# design.net
KiCad netlist of a schematic drawn in EasyEDA Pro
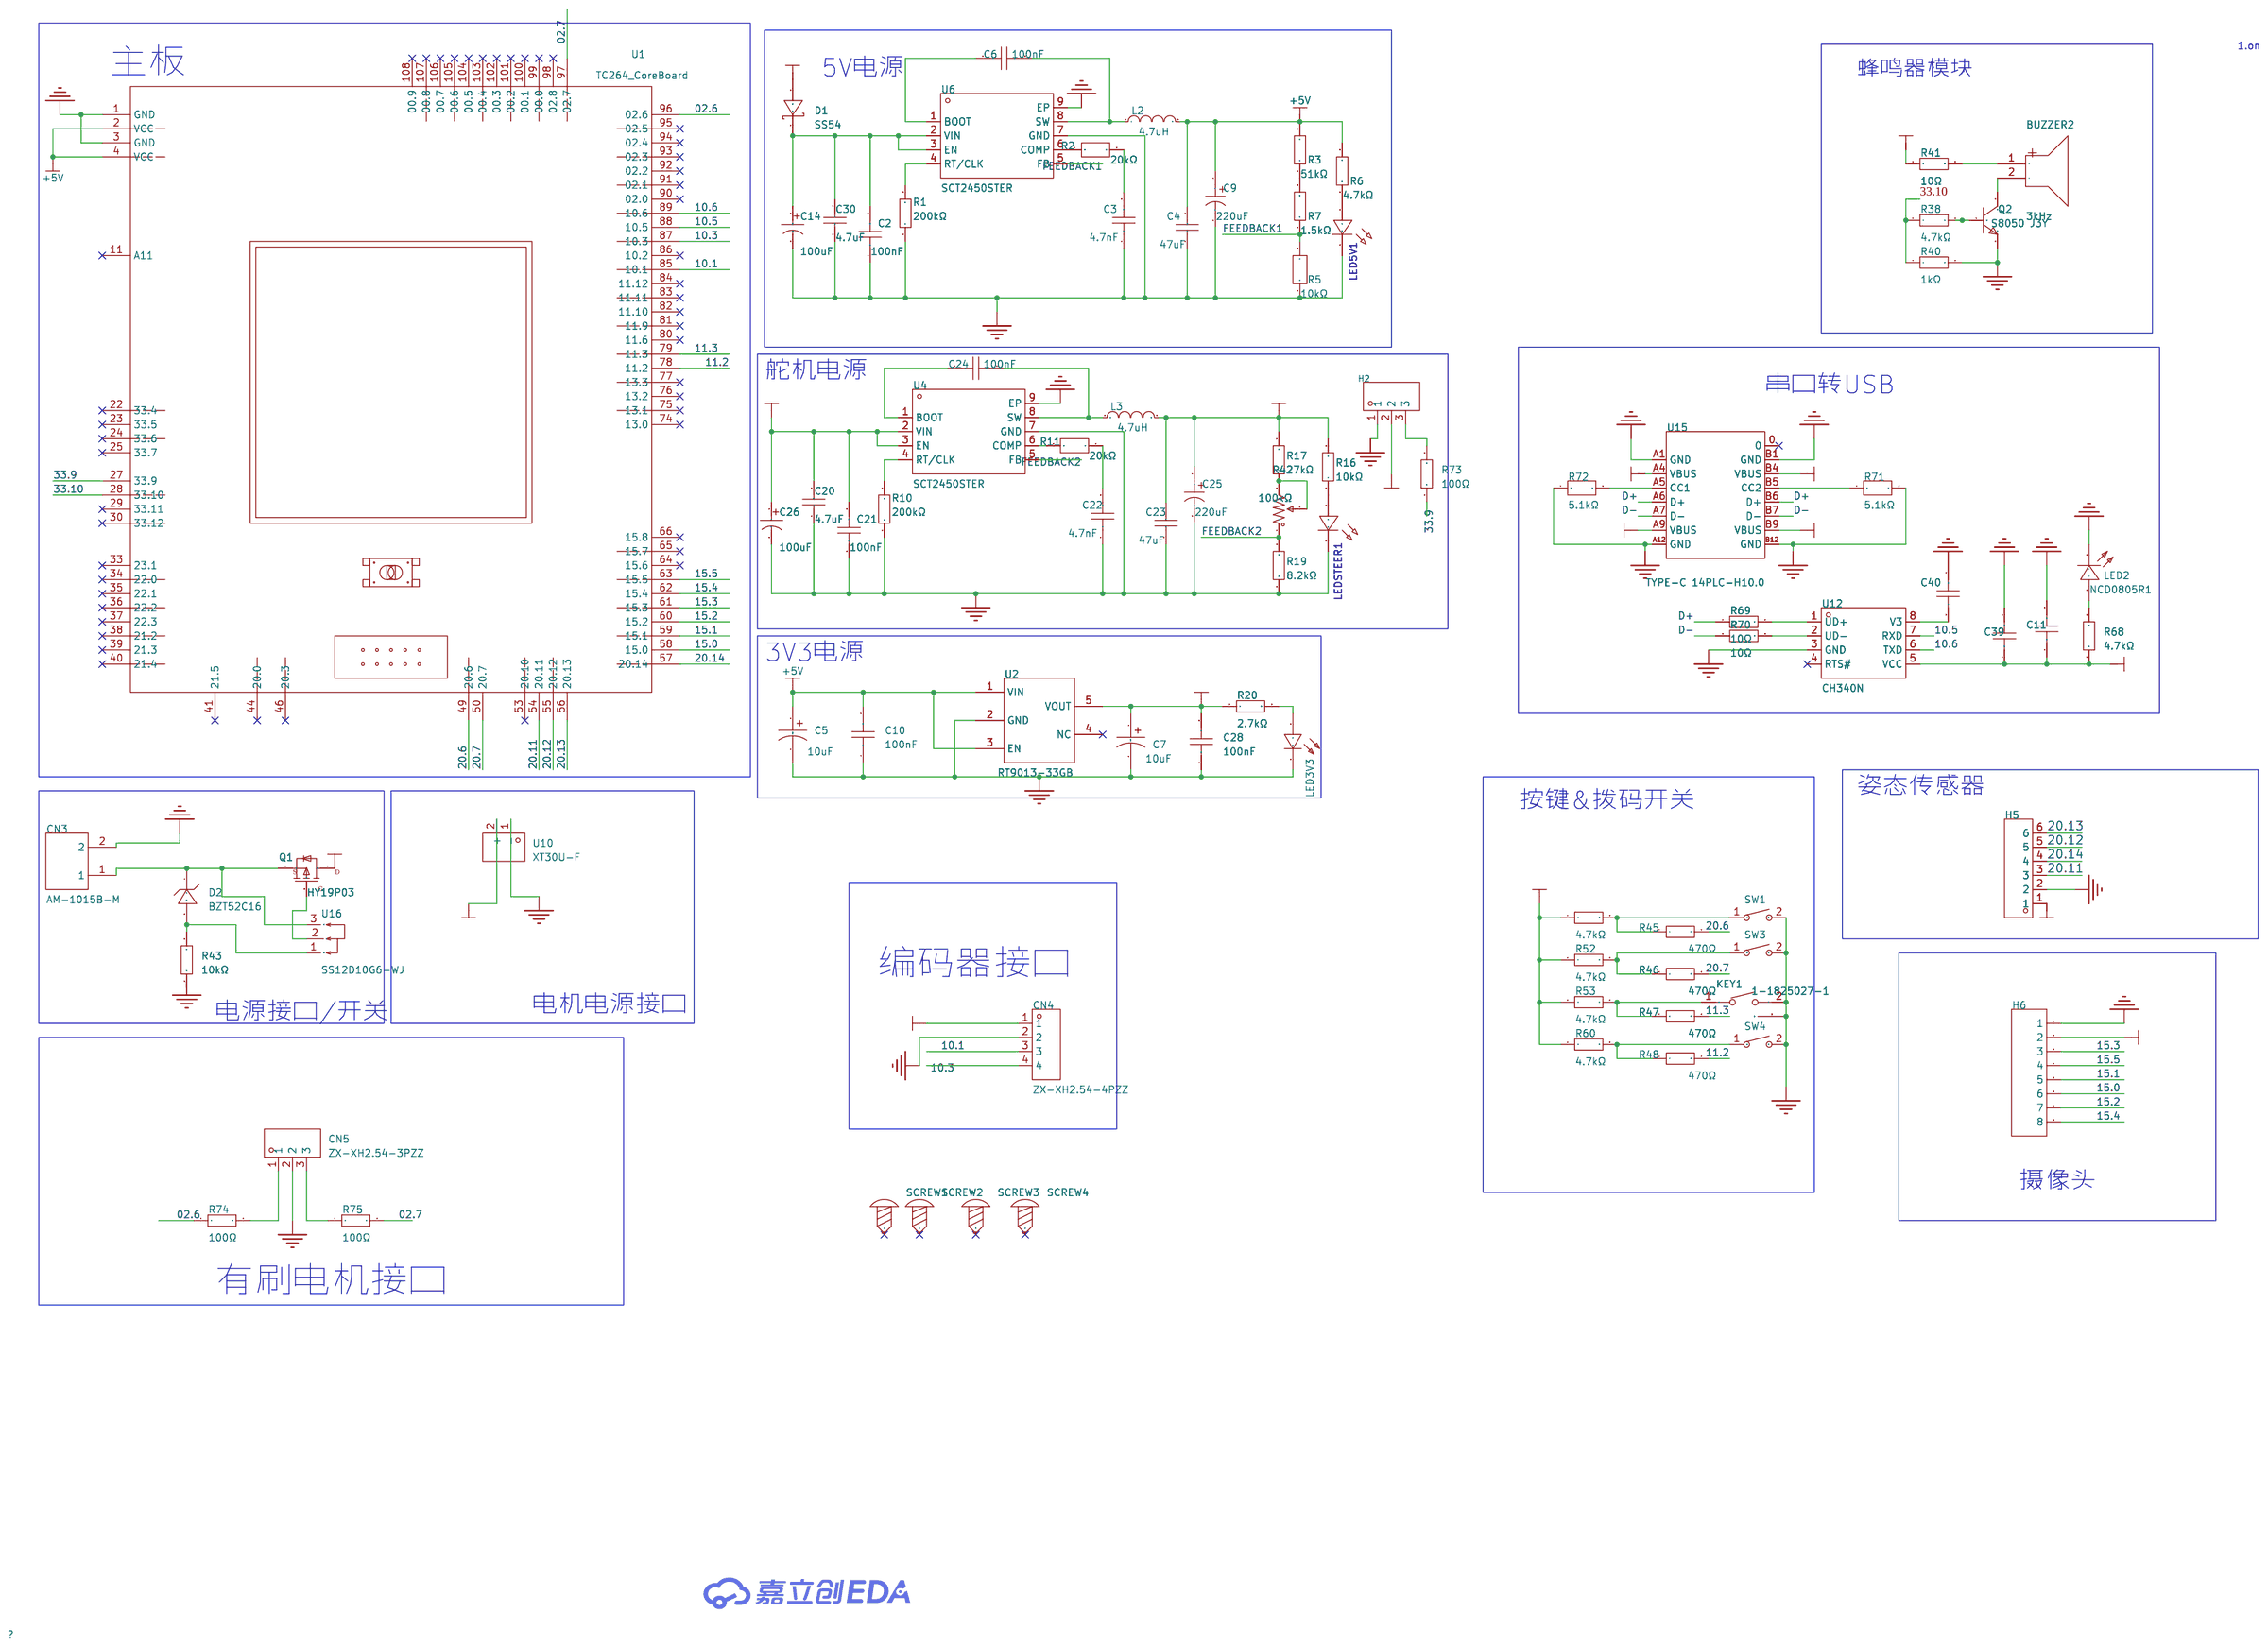
[diagram p0: schematic sheet]

(export (version "E")
  (design (tool "Eeschema 10.0.6"))
  (components
    (comp (ref "BUZZER2")
      (value "3kHz")
      (footprint "easyedapro:BUZ-TH_BD9.0-P5.00-D0.6-FD")
      (description "驱动方式:有源(内含驱动线路);构造类型:电磁式;频率:3kHz;声压(SPL):85dB;")
      (fields (field (name "Manufacturer Part") "HNB09A03") (field (name "Manufacturer") "华能"))
      (libsource (lib "easyedapro") (part "HNB09A03"))
    )
    (comp (ref "C2")
      (value "100nF")
      (footprint "easyedapro:C0603")
      (description "容值:100nF;精度:±10%;额定电压:50V;材质(温度系数):X7R;")
      (fields
        (field (name "Manufacturer Part") "CGA0603X7R104K500JT")
        (field (name "Manufacturer") "HRE(芯声)")
      )
      (libsource (lib "easyedapro") (part "CGA0603X7R104K500JT"))
    )
    (comp (ref "C3")
      (value "4.7nF")
      (footprint "easyedapro:C0603")
      (description "容值:4.7nF;精度:±10%;额定电压:50V;材质(温度系数):X7R;")
      (fields
        (field (name "Manufacturer Part") "CGA0603X7R472K500JT")
        (field (name "Manufacturer") "HRE(芯声)")
      )
      (libsource (lib "easyedapro") (part "CGA0603X7R472K500JT"))
    )
    (comp (ref "C4")
      (value "47uF")
      (footprint "easyedapro:C0603")
      (description "容值:47uF;精度:±20%;额定电压:6.3V;材质(温度系数):X5R;")
      (fields
        (field (name "Manufacturer Part") "GRM188R60J476ME15D")
        (field (name "Manufacturer") "muRata(村田)")
      )
      (libsource (lib "easyedapro") (part "GRM188R60J476ME15D"))
    )
    (comp (ref "C5")
      (value "10uF")
      (footprint "easyedapro:CAP-SMD_BD4.0-L4.3-W4.3-LS5.3-FD")
      (description "容值:10uF;精度:±20%;额定电压:16V;纹波电流:23mA@120Hz;等效串联电阻:-;")
      (fields
        (field (name "Manufacturer Part") "UWX1C100MCL1GB")
        (field (name "Manufacturer") "Nichicon(尼吉康)")
      )
      (libsource (lib "easyedapro") (part "UWX1C100MCL1GB"))
    )
    (comp (ref "C6")
      (value "100nF")
      (footprint "easyedapro:C0603")
      (description "容值:100nF;精度:±10%;额定电压:50V;材质(温度系数):X7R;")
      (fields
        (field (name "Manufacturer Part") "CGA0603X7R104K500JT")
        (field (name "Manufacturer") "HRE(芯声)")
      )
      (libsource (lib "easyedapro") (part "CGA0603X7R104K500JT"))
    )
    (comp (ref "C7")
      (value "10uF")
      (footprint "easyedapro:CAP-SMD_BD4.0-L4.3-W4.3-LS5.3-FD")
      (description "容值:10uF;精度:±20%;额定电压:16V;纹波电流:23mA@120Hz;等效串联电阻:-;")
      (fields
        (field (name "Manufacturer Part") "UWX1C100MCL1GB")
        (field (name "Manufacturer") "Nichicon(尼吉康)")
      )
      (libsource (lib "easyedapro") (part "UWX1C100MCL1GB"))
    )
    (comp (ref "C9")
      (value "220uF")
      (footprint "easyedapro:CAP-TH_BD6.3-P2.50-D0.6-FD-1")
      (description "容值:220uF;精度:±20%;额定电压:25V;纹波电流:3.1A@100kHz;等效串联电阻:18mΩ@100kHz;")
      (fields
        (field (name "Manufacturer Part") "KNE2220UF25V149EC0030")
        (field (name "Manufacturer") "KNSCHA(科尼盛)")
      )
      (libsource (lib "easyedapro") (part "KNE2220UF25V149EC0030"))
    )
    (comp (ref "C10")
      (value "100nF")
      (footprint "easyedapro:C0603")
      (description "容值:100nF;精度:±10%;额定电压:50V;材质(温度系数):X7R;")
      (fields
        (field (name "Manufacturer Part") "CGA0603X7R104K500JT")
        (field (name "Manufacturer") "HRE(芯声)")
      )
      (libsource (lib "easyedapro") (part "CGA0603X7R104K500JT"))
    )
    (comp (ref "C11")
      (value "100nF")
      (footprint "easyedapro:C0603")
      (description "容值:100nF;精度:±10%;额定电压:50V;材质(温度系数):X7R;")
      (fields
        (field (name "Manufacturer Part") "CC0603KRX7R9BB104")
        (field (name "Manufacturer") "YAGEO(国巨)")
      )
      (libsource (lib "easyedapro") (part "CC0603KRX7R9BB104"))
    )
    (comp (ref "C14")
      (value "100uF")
      (footprint "easyedapro:CAP-TH_BD6.3-P2.50-D1.0-FD")
      (description "容值:100uF;精度:±20%;额定电压:35V;纹波电流:2.35A@100kHz;等效串联电阻:50mΩ@100kHz;类型:-;")
      (fields
        (field (name "Manufacturer Part") "SPZ1VM101E08O00RAXXX")
        (field (name "Manufacturer") "AISHI(艾华集团)")
      )
      (libsource (lib "easyedapro") (part "SPZ1VM101E08000R"))
    )
    (comp (ref "C20")
      (value "4.7uF")
      (footprint "easyedapro:C0603")
      (description "容值:4.7uF;精度:±10%;额定电压:16V;材质(温度系数):X5R;")
      (fields
        (field (name "Manufacturer Part") "CL10A475KO8NNNC")
        (field (name "Manufacturer") "SAMSUNG(三星)")
      )
      (libsource (lib "easyedapro") (part "CL10A475KO8NNNC"))
    )
    (comp (ref "C21")
      (value "100nF")
      (footprint "easyedapro:C0603")
      (description "容值:100nF;精度:±10%;额定电压:50V;材质(温度系数):X7R;")
      (fields
        (field (name "Manufacturer Part") "CGA0603X7R104K500JT")
        (field (name "Manufacturer") "HRE(芯声)")
      )
      (libsource (lib "easyedapro") (part "CGA0603X7R104K500JT"))
    )
    (comp (ref "C22")
      (value "4.7nF")
      (footprint "easyedapro:C0603")
      (description "容值:4.7nF;精度:±10%;额定电压:50V;材质(温度系数):X7R;")
      (fields
        (field (name "Manufacturer Part") "CGA0603X7R472K500JT")
        (field (name "Manufacturer") "HRE(芯声)")
      )
      (libsource (lib "easyedapro") (part "CGA0603X7R472K500JT"))
    )
    (comp (ref "C23")
      (value "47uF")
      (footprint "easyedapro:C0603")
      (description "容值:47uF;精度:±20%;额定电压:6.3V;材质(温度系数):X5R;")
      (fields
        (field (name "Manufacturer Part") "GRM188R60J476ME15D")
        (field (name "Manufacturer") "muRata(村田)")
      )
      (libsource (lib "easyedapro") (part "GRM188R60J476ME15D"))
    )
    (comp (ref "C24")
      (value "100nF")
      (footprint "easyedapro:C0603")
      (description "容值:100nF;精度:±10%;额定电压:50V;材质(温度系数):X7R;")
      (fields
        (field (name "Manufacturer Part") "CGA0603X7R104K500JT")
        (field (name "Manufacturer") "HRE(芯声)")
      )
      (libsource (lib "easyedapro") (part "CGA0603X7R104K500JT"))
    )
    (comp (ref "C25")
      (value "220uF")
      (footprint "easyedapro:CAP-TH_BD6.3-P2.50-D0.6-FD-1")
      (description "容值:220uF;精度:±20%;额定电压:25V;纹波电流:3.1A@100kHz;等效串联电阻:18mΩ@100kHz;")
      (fields
        (field (name "Manufacturer Part") "KNE2220UF25V149EC0030")
        (field (name "Manufacturer") "KNSCHA(科尼盛)")
      )
      (libsource (lib "easyedapro") (part "KNE2220UF25V149EC0030"))
    )
    (comp (ref "C26")
      (value "100uF")
      (footprint "easyedapro:CAP-TH_BD6.3-P2.50-D1.0-FD")
      (description "容值:100uF;精度:±20%;额定电压:35V;纹波电流:2.35A@100kHz;等效串联电阻:50mΩ@100kHz;类型:-;")
      (fields
        (field (name "Manufacturer Part") "SPZ1VM101E08O00RAXXX")
        (field (name "Manufacturer") "AISHI(艾华集团)")
      )
      (libsource (lib "easyedapro") (part "SPZ1VM101E08000R"))
    )
    (comp (ref "C28")
      (value "100nF")
      (footprint "easyedapro:C0603")
      (description "容值:100nF;精度:±10%;额定电压:50V;材质(温度系数):X7R;")
      (fields
        (field (name "Manufacturer Part") "CGA0603X7R104K500JT")
        (field (name "Manufacturer") "HRE(芯声)")
      )
      (libsource (lib "easyedapro") (part "CGA0603X7R104K500JT"))
    )
    (comp (ref "C30")
      (value "4.7uF")
      (footprint "easyedapro:C0603")
      (description "容值:4.7uF;精度:±10%;额定电压:16V;材质(温度系数):X5R;")
      (fields
        (field (name "Manufacturer Part") "CL10A475KO8NNNC")
        (field (name "Manufacturer") "SAMSUNG(三星)")
      )
      (libsource (lib "easyedapro") (part "CL10A475KO8NNNC"))
    )
    (comp (ref "C39")
      (value "100nF")
      (footprint "easyedapro:C0603")
      (description "容值:100nF;精度:±10%;额定电压:50V;材质(温度系数):X7R;")
      (fields
        (field (name "Manufacturer Part") "CC0603KRX7R9BB104")
        (field (name "Manufacturer") "YAGEO(国巨)")
      )
      (libsource (lib "easyedapro") (part "CC0603KRX7R9BB104"))
    )
    (comp (ref "C40")
      (value "100nF")
      (footprint "easyedapro:C0603")
      (description "容值:100nF;精度:±10%;额定电压:50V;材质(温度系数):X7R;")
      (fields
        (field (name "Manufacturer Part") "CC0603KRX7R9BB104")
        (field (name "Manufacturer") "YAGEO(国巨)")
      )
      (libsource (lib "easyedapro") (part "CC0603KRX7R9BB104"))
    )
    (comp (ref "CN3")
      (value "AM-1015B-M")
      (footprint "easyedapro:CONN-TH_AM-1015B-M")
      (description "类别:-;类型1:-;")
      (fields (field (name "Manufacturer") "AMASS(艾迈斯)"))
      (libsource (lib "easyedapro") (part "AM-1015B-M"))
    )
    (comp (ref "CN4")
      (value "ZX-XH2.54-4PZZ")
      (footprint "easyedapro:CONN-TH_4P-P2.50_4PIN")
      (fields (field (name "Manufacturer") "Megastar(兆星)"))
      (libsource (lib "easyedapro") (part "ZX-XH2.54-4PZZ"))
    )
    (comp (ref "CN5")
      (value "ZX-XH2.54-3PZZ")
      (footprint "easyedapro:CONN-TH_3P-P2.54_2501S-3P")
      (fields (field (name "Manufacturer") "Megastar(兆星)"))
      (libsource (lib "easyedapro") (part "ZX-XH2.54-3PZZ"))
    )
    (comp (ref "D1")
      (value "SS54")
      (footprint "easyedapro:SMA_L4.4-W2.8-LS5.4-R-RD")
      (description "直流反向耐压(Vr):40V;平均整流电流(Io):5A;正向压降(Vf):550mV@5A;")
      (fields (field (name "Manufacturer") "MDD"))
      (libsource (lib "easyedapro") (part "SS54_C22452"))
    )
    (comp (ref "D2")
      (value "BZT52C16")
      (footprint "easyedapro:SOD-123_L2.7-W1.6-LS3.7-RD")
      (description "二极管配置:独立式;稳压值(标称值):16V;稳压值(范围):15.3V~17.1V;功率:500mW;精度:-;")
      (fields (field (name "Manufacturer") "BORN(伯恩半导体)"))
      (libsource (lib "easyedapro") (part "BZT52C16_C266570"))
    )
    (comp (ref "H2")
      (value "PZ254V-11-03P")
      (footprint "easyedapro:HDR-TH_3P-P2.54-V-M")
      (fields (field (name "Manufacturer") "XFCN(兴飞)"))
      (libsource (lib "easyedapro") (part "PZ254V-11-03P_C2937625"))
    )
    (comp (ref "H5")
      (value "PZ254V-11-06P")
      (footprint "easyedapro:HDR-TH_6P-P2.54-V-M")
      (fields (field (name "Manufacturer") "XFCN(兴飞)"))
      (libsource (lib "easyedapro") (part "PZ254V-11-06P"))
    )
    (comp (ref "H6")
      (value "~")
      (footprint "easyedapro:HDR-TH_8P-P2.54-V-M")
      (libsource (lib "easyedapro") (part "Header-Male-2.54_1x8"))
    )
    (comp (ref "KEY1")
      (value "1-1825027-1")
      (footprint "easyedapro:KEY-TH_1-1825027-1")
      (description "电路结构:单刀单掷;按钮形状:圆形按钮;作用力:160gf;安装方式:卧插;开关高度:5.74mm;触点电流:50mA;额定电压(DC):24V;带灯:-;机械寿命:-;")
      (fields (field (name "Manufacturer") "TE Connectivity(泰科电子)"))
      (libsource (lib "easyedapro") (part "1-1825027-1"))
    )
    (comp (ref "L2")
      (value "4.7uH")
      (footprint "easyedapro:IND-SMD_L5.4-W5.2_FXL0530")
      (description "电感值:4.7uH;精度:±20%;额定电流:4.5A;饱和电流(Isat):5A;类型:一体成型电感;")
      (fields (field (name "Manufacturer Part") "FXL0530-4R7-M") (field (name "Manufacturer") "cjiang(长江微电)"))
      (libsource (lib "easyedapro") (part "FXL0530-4R7-M"))
    )
    (comp (ref "L3")
      (value "4.7uH")
      (footprint "easyedapro:IND-SMD_L5.4-W5.2_FXL0530")
      (description "电感值:4.7uH;精度:±20%;额定电流:4.5A;饱和电流(Isat):5A;类型:一体成型电感;")
      (fields (field (name "Manufacturer Part") "FXL0530-4R7-M") (field (name "Manufacturer") "cjiang(长江微电)"))
      (libsource (lib "easyedapro") (part "FXL0530-4R7-M"))
    )
    (comp (ref "LED2")
      (value "NCD0805R1")
      (footprint "easyedapro:LED0805-RD")
      (description "发光颜色:红灯;")
      (fields (field (name "Manufacturer") "国星光电"))
      (libsource (lib "easyedapro") (part "FC-2012HRK-620D"))
    )
    (comp (ref "LED3V3")
      (value "SML-H12P8TT86")
      (footprint "easyedapro:LED0805-R-RD_GREEN")
      (description "发光颜色:普绿/黄绿;二极管配置:-;透镜颜色:-;主波长:560nm;峰值波长:-;色温:-;测试电流:20mA;功率:54mW;发光角度:-;安装方式:-;工作温度:-40°C~+85°C;")
      (fields (field (name "Manufacturer") "ROHM(罗姆)"))
      (libsource (lib "easyedapro") (part "SML-H12P8TT86"))
    )
    (comp (ref "LED5V1")
      (value "~")
      (footprint "easyedapro:LED_0805")
      (libsource (lib "easyedapro") (part "LED_G"))
    )
    (comp (ref "LEDSTEER1")
      (value "~")
      (footprint "easyedapro:LED_0805")
      (libsource (lib "easyedapro") (part "LED_G"))
    )
    (comp (ref "Q1")
      (value "HY19P03")
      (footprint "easyedapro:TO-252AA-TO-252AA_N")
      (libsource (lib "easyedapro") (part "HY19P03"))
    )
    (comp (ref "Q2")
      (value "S8050 J3Y")
      (footprint "easyedapro:SOT-23-3_L3.0-W1.7-P0.95-LS2.9-BR")
      (fields (field (name "Manufacturer") "CJ（江苏长电/长晶）"))
      (libsource (lib "easyedapro") (part "S8050_C2146"))
    )
    (comp (ref "R1")
      (value "200kΩ")
      (footprint "easyedapro:R0603")
      (description "电阻类型:厚膜电阻;阻值:200kΩ;精度:±1%;功率:100mW;最大工作电压:75V;温度系数:±100ppm/°C;")
      (fields
        (field (name "Manufacturer Part") "0603WAF2003T5E")
        (field (name "Manufacturer") "UNI-ROYAL(厚声)")
      )
      (libsource (lib "easyedapro") (part "0603WAF2003T5E"))
    )
    (comp (ref "R2")
      (value "20kΩ")
      (footprint "easyedapro:R0603")
      (description "电阻类型:薄膜电阻;阻值:20kΩ;精度:±0.1%;功率:100mW;最大工作电压:75V;温度系数:±25ppm/°C;")
      (fields (field (name "Manufacturer Part") "RT0603BRD0720KL") (field (name "Manufacturer") "YAGEO(国巨)"))
      (libsource (lib "easyedapro") (part "RT0603BRD0720KL"))
    )
    (comp (ref "R3")
      (value "51kΩ")
      (footprint "easyedapro:R0603")
      (description "电阻类型:厚膜电阻;阻值:51kΩ;精度:±1%;功率:100mW;最大工作电压:75V;温度系数:±100ppm/°C;")
      (fields
        (field (name "Manufacturer Part") "0603WAF5102T5E")
        (field (name "Manufacturer") "UNI-ROYAL(厚声)")
      )
      (libsource (lib "easyedapro") (part "0603WAF5102T5E"))
    )
    (comp (ref "R5")
      (value "10kΩ")
      (footprint "easyedapro:R0603")
      (description "电阻类型:厚膜电阻;阻值:10kΩ;精度:±5%;功率:100mW;最大工作电压:75V;温度系数:±100ppm/°C;")
      (fields (field (name "Manufacturer Part") "FRC0603J103TS") (field (name "Manufacturer") "FOJAN(富捷)"))
      (libsource (lib "easyedapro") (part "FRC0603J103TS"))
    )
    (comp (ref "R6")
      (value "4.7kΩ")
      (footprint "easyedapro:R0603")
      (description "电阻类型:厚膜电阻;阻值:4.7kΩ;精度:±1%;功率:100mW;最大工作电压:75V;温度系数:±100ppm/°C;")
      (fields (field (name "Manufacturer Part") "RC0603FR-074K7L") (field (name "Manufacturer") "YAGEO(国巨)"))
      (libsource (lib "easyedapro") (part "RC0603FR-074K7L"))
    )
    (comp (ref "R7")
      (value "1.5kΩ")
      (footprint "easyedapro:R0603")
      (description "电阻类型:厚膜电阻;阻值:1.5kΩ;精度:±1%;功率:100mW;最大工作电压:75V;温度系数:±100ppm/°C;")
      (fields
        (field (name "Manufacturer Part") "0603WAF1501T5E")
        (field (name "Manufacturer") "UNI-ROYAL(厚声)")
      )
      (libsource (lib "easyedapro") (part "0603WAF1501T5E"))
    )
    (comp (ref "R10")
      (value "200kΩ")
      (footprint "easyedapro:R0603")
      (description "电阻类型:厚膜电阻;阻值:200kΩ;精度:±1%;功率:100mW;最大工作电压:75V;温度系数:±100ppm/°C;")
      (fields
        (field (name "Manufacturer Part") "0603WAF2003T5E")
        (field (name "Manufacturer") "UNI-ROYAL(厚声)")
      )
      (libsource (lib "easyedapro") (part "0603WAF2003T5E"))
    )
    (comp (ref "R11")
      (value "20kΩ")
      (footprint "easyedapro:R0603")
      (description "电阻类型:薄膜电阻;阻值:20kΩ;精度:±0.1%;功率:100mW;最大工作电压:75V;温度系数:±25ppm/°C;")
      (fields (field (name "Manufacturer Part") "RT0603BRD0720KL") (field (name "Manufacturer") "YAGEO(国巨)"))
      (libsource (lib "easyedapro") (part "RT0603BRD0720KL"))
    )
    (comp (ref "R16")
      (value "10kΩ")
      (footprint "easyedapro:R0603")
      (description "电阻类型:厚膜电阻;阻值:10kΩ;精度:±1%;功率:100mW;最大工作电压:75V;温度系数:±100ppm/°C;")
      (fields
        (field (name "Manufacturer Part") "0603WAF1002T5E")
        (field (name "Manufacturer") "UNI-ROYAL(厚声)")
      )
      (libsource (lib "easyedapro") (part "0603WAF1002T5E"))
    )
    (comp (ref "R17")
      (value "27kΩ")
      (footprint "easyedapro:R0603")
      (description "电阻类型:厚膜电阻;阻值:27kΩ;精度:±1%;功率:100mW;最大工作电压:75V;温度系数:±100ppm/°C;")
      (fields
        (field (name "Manufacturer Part") "0603WAF2702T5E")
        (field (name "Manufacturer") "UNI-ROYAL(厚声)")
      )
      (libsource (lib "easyedapro") (part "0603WAF2702T5E"))
    )
    (comp (ref "R19")
      (value "8.2kΩ")
      (footprint "easyedapro:R0603")
      (description "电阻类型:厚膜电阻;阻值:8.2kΩ;精度:±1%;功率:100mW;最大工作电压:75V;温度系数:±100ppm/°C;")
      (fields
        (field (name "Manufacturer Part") "0603WAF8201T5E")
        (field (name "Manufacturer") "UNI-ROYAL(厚声)")
      )
      (libsource (lib "easyedapro") (part "0603WAF8201T5E"))
    )
    (comp (ref "R20")
      (value "2.7kΩ")
      (footprint "easyedapro:R0603")
      (description "电阻类型:厚膜电阻;阻值:2.7kΩ;精度:±1%;功率:100mW;最大工作电压:75V;温度系数:±100ppm/°C;")
      (fields
        (field (name "Manufacturer Part") "0603WAF2701T5E")
        (field (name "Manufacturer") "UNI-ROYAL(厚声)")
      )
      (libsource (lib "easyedapro") (part "0603WAF2701T5E"))
    )
    (comp (ref "R38")
      (value "4.7kΩ")
      (footprint "easyedapro:R0603")
      (description "电阻类型:厚膜电阻;阻值:4.7kΩ;精度:±1%;功率:100mW;最大工作电压:75V;温度系数:±100ppm/°C;")
      (fields
        (field (name "Manufacturer Part") "0603WAF4701T5E")
        (field (name "Manufacturer") "UNI-ROYAL(厚声)")
      )
      (libsource (lib "easyedapro") (part "0603WAF4701T5E"))
    )
    (comp (ref "R40")
      (value "1kΩ")
      (footprint "easyedapro:R0603")
      (description "电阻类型:厚膜电阻;阻值:1kΩ;精度:±1%;功率:100mW;最大工作电压:75V;温度系数:±100ppm/°C;")
      (fields
        (field (name "Manufacturer Part") "0603WAF1001T5E")
        (field (name "Manufacturer") "UNI-ROYAL(厚声)")
      )
      (libsource (lib "easyedapro") (part "0603WAF1001T5E"))
    )
    (comp (ref "R41")
      (value "10Ω")
      (footprint "easyedapro:R0603")
      (description "电阻类型:厚膜电阻;阻值:10Ω;精度:±1%;功率:100mW;最大工作电压:75V;温度系数:±400ppm/°C;")
      (fields
        (field (name "Manufacturer Part") "0603WAF100JT5E")
        (field (name "Manufacturer") "UNI-ROYAL(厚声)")
      )
      (libsource (lib "easyedapro") (part "0603WAF100JT5E"))
    )
    (comp (ref "R42")
      (value "100kΩ")
      (footprint "easyedapro:RES-ADJ-TH_3P-L9.7-W5.0-P2.54_T93YA203KT20")
      (description "阻值:100kΩ;精度:±10%;功率:500mW;温度系数:±100ppm/°C;")
      (fields (field (name "Manufacturer Part") "T93YA104KT20") (field (name "Manufacturer") "VISHAY(威世)"))
      (libsource (lib "easyedapro") (part "T93YA104KT20"))
    )
    (comp (ref "R43")
      (value "10kΩ")
      (footprint "easyedapro:R0805")
      (description "电阻类型:厚膜电阻;阻值:10kΩ;精度:±1%;功率:125mW;最大工作电压:150V;温度系数:±100ppm/°C;")
      (fields
        (field (name "Manufacturer Part") "0805W8F1002T5E")
        (field (name "Manufacturer") "UNI-ROYAL(厚声)")
      )
      (libsource (lib "easyedapro") (part "0805W8F1002T5E"))
    )
    (comp (ref "R45")
      (value "470Ω")
      (footprint "easyedapro:R0603")
      (description "电阻类型:厚膜电阻;阻值:470Ω;精度:±1%;功率:100mW;最大工作电压:75V;温度系数:±100ppm/°C;")
      (fields
        (field (name "Manufacturer Part") "0603WAF4700T5E")
        (field (name "Manufacturer") "UNI-ROYAL(厚声)")
      )
      (libsource (lib "easyedapro") (part "0603WAF4700T5E"))
    )
    (comp (ref "R46")
      (value "470Ω")
      (footprint "easyedapro:R0603")
      (description "电阻类型:厚膜电阻;阻值:470Ω;精度:±1%;功率:100mW;最大工作电压:75V;温度系数:±100ppm/°C;")
      (fields
        (field (name "Manufacturer Part") "0603WAF4700T5E")
        (field (name "Manufacturer") "UNI-ROYAL(厚声)")
      )
      (libsource (lib "easyedapro") (part "0603WAF4700T5E"))
    )
    (comp (ref "R47")
      (value "470Ω")
      (footprint "easyedapro:R0603")
      (description "电阻类型:厚膜电阻;阻值:470Ω;精度:±1%;功率:100mW;最大工作电压:75V;温度系数:±100ppm/°C;")
      (fields
        (field (name "Manufacturer Part") "0603WAF4700T5E")
        (field (name "Manufacturer") "UNI-ROYAL(厚声)")
      )
      (libsource (lib "easyedapro") (part "0603WAF4700T5E"))
    )
    (comp (ref "R48")
      (value "470Ω")
      (footprint "easyedapro:R0603")
      (description "电阻类型:厚膜电阻;阻值:470Ω;精度:±1%;功率:100mW;最大工作电压:75V;温度系数:±100ppm/°C;")
      (fields
        (field (name "Manufacturer Part") "0603WAF4700T5E")
        (field (name "Manufacturer") "UNI-ROYAL(厚声)")
      )
      (libsource (lib "easyedapro") (part "0603WAF4700T5E"))
    )
    (comp (ref "R51")
      (value "4.7kΩ")
      (footprint "easyedapro:R0603")
      (description "电阻类型:厚膜电阻;阻值:4.7kΩ;精度:±1%;功率:100mW;最大工作电压:75V;温度系数:±100ppm/°C;")
      (fields
        (field (name "Manufacturer Part") "0603WAF4701T5E")
        (field (name "Manufacturer") "UNI-ROYAL(厚声)")
      )
      (libsource (lib "easyedapro") (part "0603WAF4701T5E"))
    )
    (comp (ref "R52")
      (value "4.7kΩ")
      (footprint "easyedapro:R0603")
      (description "电阻类型:厚膜电阻;阻值:4.7kΩ;精度:±1%;功率:100mW;最大工作电压:75V;温度系数:±100ppm/°C;")
      (fields
        (field (name "Manufacturer Part") "0603WAF4701T5E")
        (field (name "Manufacturer") "UNI-ROYAL(厚声)")
      )
      (libsource (lib "easyedapro") (part "0603WAF4701T5E"))
    )
    (comp (ref "R53")
      (value "4.7kΩ")
      (footprint "easyedapro:R0603")
      (description "电阻类型:厚膜电阻;阻值:4.7kΩ;精度:±1%;功率:100mW;最大工作电压:75V;温度系数:±100ppm/°C;")
      (fields
        (field (name "Manufacturer Part") "0603WAF4701T5E")
        (field (name "Manufacturer") "UNI-ROYAL(厚声)")
      )
      (libsource (lib "easyedapro") (part "0603WAF4701T5E"))
    )
    (comp (ref "R60")
      (value "4.7kΩ")
      (footprint "easyedapro:R0603")
      (description "电阻类型:厚膜电阻;阻值:4.7kΩ;精度:±1%;功率:100mW;最大工作电压:75V;温度系数:±100ppm/°C;")
      (fields
        (field (name "Manufacturer Part") "0603WAF4701T5E")
        (field (name "Manufacturer") "UNI-ROYAL(厚声)")
      )
      (libsource (lib "easyedapro") (part "0603WAF4701T5E"))
    )
    (comp (ref "R68")
      (value "4.7kΩ")
      (footprint "easyedapro:R0603")
      (description "电阻类型:厚膜电阻;阻值:4.7kΩ;精度:±1%;功率:100mW;最大工作电压:75V;温度系数:±100ppm/°C;")
      (fields
        (field (name "Manufacturer Part") "0603WAF4701T5E")
        (field (name "Manufacturer") "UNI-ROYAL(厚声)")
      )
      (libsource (lib "easyedapro") (part "0603WAF4701T5E"))
    )
    (comp (ref "R69")
      (value "10Ω")
      (footprint "easyedapro:R0603")
      (description "电阻类型:厚膜电阻;阻值:10Ω;精度:±1%;功率:100mW;最大工作电压:75V;温度系数:±400ppm/°C;")
      (fields
        (field (name "Manufacturer Part") "0603WAF100JT5E")
        (field (name "Manufacturer") "UNI-ROYAL(厚声)")
      )
      (libsource (lib "easyedapro") (part "0603WAF100JT5E"))
    )
    (comp (ref "R70")
      (value "10Ω")
      (footprint "easyedapro:R0603")
      (description "电阻类型:厚膜电阻;阻值:10Ω;精度:±1%;功率:100mW;最大工作电压:75V;温度系数:±400ppm/°C;")
      (fields
        (field (name "Manufacturer Part") "0603WAF100JT5E")
        (field (name "Manufacturer") "UNI-ROYAL(厚声)")
      )
      (libsource (lib "easyedapro") (part "0603WAF100JT5E"))
    )
    (comp (ref "R71")
      (value "5.1kΩ")
      (footprint "easyedapro:R0603")
      (description "电阻类型:厚膜电阻;阻值:5.1kΩ;精度:±1%;功率:100mW;最大工作电压:75V;温度系数:±100ppm/°C;")
      (fields (field (name "Manufacturer Part") "FRC0603F5101TS") (field (name "Manufacturer") "FOJAN(富捷)"))
      (libsource (lib "easyedapro") (part "FRC0603F5101TS"))
    )
    (comp (ref "R72")
      (value "5.1kΩ")
      (footprint "easyedapro:R0603")
      (description "电阻类型:厚膜电阻;阻值:5.1kΩ;精度:±1%;功率:100mW;最大工作电压:75V;温度系数:±100ppm/°C;")
      (fields (field (name "Manufacturer Part") "FRC0603F5101TS") (field (name "Manufacturer") "FOJAN(富捷)"))
      (libsource (lib "easyedapro") (part "FRC0603F5101TS"))
    )
    (comp (ref "R73")
      (value "100Ω")
      (footprint "easyedapro:R0603")
      (description "阻值:100Ω;精度:±1%;功率:100mW;温度系数:±200ppm/°C;电阻类型:厚膜电阻;")
      (fields
        (field (name "Manufacturer Part") "0603WAF1000T5E")
        (field (name "Manufacturer") "UNI-ROYAL(厚声)")
      )
      (libsource (lib "easyedapro") (part "0603WAF1000T5E"))
    )
    (comp (ref "R74")
      (value "100Ω")
      (footprint "easyedapro:R0603")
      (description "阻值:100Ω;精度:±1%;功率:100mW;温度系数:±200ppm/°C;电阻类型:厚膜电阻;")
      (fields
        (field (name "Manufacturer Part") "0603WAF1000T5E")
        (field (name "Manufacturer") "UNI-ROYAL(厚声)")
      )
      (libsource (lib "easyedapro") (part "0603WAF1000T5E"))
    )
    (comp (ref "R75")
      (value "100Ω")
      (footprint "easyedapro:R0603")
      (description "阻值:100Ω;精度:±1%;功率:100mW;温度系数:±200ppm/°C;电阻类型:厚膜电阻;")
      (fields
        (field (name "Manufacturer Part") "0603WAF1000T5E")
        (field (name "Manufacturer") "UNI-ROYAL(厚声)")
      )
      (libsource (lib "easyedapro") (part "0603WAF1000T5E"))
    )
    (comp (ref "SCREW1")
      (value "~")
      (footprint "easyedapro:M2螺丝")
      (libsource (lib "easyedapro") (part "螺丝孔"))
    )
    (comp (ref "SCREW2")
      (value "~")
      (footprint "easyedapro:M2螺丝")
      (libsource (lib "easyedapro") (part "螺丝孔"))
    )
    (comp (ref "SCREW3")
      (value "~")
      (footprint "easyedapro:M2螺丝")
      (libsource (lib "easyedapro") (part "螺丝孔"))
    )
    (comp (ref "SCREW4")
      (value "~")
      (footprint "easyedapro:M2螺丝")
      (libsource (lib "easyedapro") (part "螺丝孔"))
    )
    (comp (ref "SW1")
      (value "TS665WS 200gf(016)")
      (footprint "easyedapro:SW-SMD_L6.0-W6.0-P6.00-LS6.6")
      (fields (field (name "Manufacturer") "SHOU HAN(首韩)"))
      (libsource (lib "easyedapro") (part "TS665WS 200GF(016)"))
    )
    (comp (ref "SW3")
      (value "TS665WS 200gf(016)")
      (footprint "easyedapro:SW-SMD_L6.0-W6.0-P6.00-LS6.6")
      (fields (field (name "Manufacturer") "SHOU HAN(首韩)"))
      (libsource (lib "easyedapro") (part "TS665WS 200GF(016)"))
    )
    (comp (ref "SW4")
      (value "TS665WS 200gf(016)")
      (footprint "easyedapro:SW-SMD_L6.0-W6.0-P6.00-LS6.6")
      (fields (field (name "Manufacturer") "SHOU HAN(首韩)"))
      (libsource (lib "easyedapro") (part "TS665WS 200GF(016)"))
    )
    (comp (ref "U1")
      (value "TC264_CoreBoard")
      (footprint "easyedapro:TC264_main")
      (libsource (lib "easyedapro") (part "TC264"))
    )
    (comp (ref "U2")
      (value "RT9013-33GB")
      (footprint "easyedapro:SOT-23-5_L3.0-W1.7-P0.95-LS2.8-BL")
      (description "输出类型:固定;最大输入电压:5.5V;输出电压:3.3V;最大输出电流:500mA;电源纹波抑制比(PSRR):50dB@(10kHz);输出极性:正极;")
      (fields (field (name "Manufacturer") "RICHTEK(立锜)"))
      (libsource (lib "easyedapro") (part "RT9013-33GB"))
    )
    (comp (ref "U4")
      (value "SCT2450STER")
      (footprint "easyedapro:ESOP-8_L4.9-W3.9-P1.27-LS6.0-BL-EP")
      (fields (field (name "Manufacturer") "SCT(芯洲科技)"))
      (libsource (lib "easyedapro") (part "SCT2450STER"))
    )
    (comp (ref "U6")
      (value "SCT2450STER")
      (footprint "easyedapro:ESOP-8_L4.9-W3.9-P1.27-LS6.0-BL-EP")
      (fields (field (name "Manufacturer") "SCT(芯洲科技)"))
      (libsource (lib "easyedapro") (part "SCT2450STER"))
    )
    (comp (ref "U10")
      (value "XT30U-F")
      (footprint "easyedapro:CONN-TH_XT30U-F")
      (description "类别:-;类型1:-;")
      (fields (field (name "Manufacturer") "AMASS(艾迈斯)"))
      (libsource (lib "easyedapro") (part "XT30U-F"))
    )
    (comp (ref "U12")
      (value "CH340N")
      (footprint "easyedapro:SOP-8_L4.9-W3.9-P1.27-LS6.0-BL")
      (fields (field (name "Manufacturer") "WCH(南京沁恒)"))
      (libsource (lib "easyedapro") (part "CH340N_C2977777"))
    )
    (comp (ref "U15")
      (value "TYPE-C 14PLC-H10.0")
      (footprint "easyedapro:USB-C-TH_SHOUHAN_TYPE-C-14PLC-H10.0")
      (fields (field (name "Manufacturer") "SHOU HAN(首韩)"))
      (libsource (lib "easyedapro") (part "TYPE-C 14PLC-H10.0"))
    )
    (comp (ref "U16")
      (value "SS12D10G6-WJ")
      (footprint "easyedapro:SW-TH_3P-P4.80_HX-SS12D10G6-WJ")
      (description "电路结构:单刀双掷;安装方式:弯插;开关颜色:黑色;额定电流:2A;额定电压:125V;工作寿命:3千次;")
      (fields (field (name "Manufacturer") "SHOU HAN(首韩)"))
      (libsource (lib "easyedapro") (part "SS12D10G6-WJ"))
    )
  )
  (nets
    (net (code "1") (name "+5V") (class "Default")
      (node (ref "C10") (pin "2") (pinfunction "2_2") (pintype "unspecified"))
      (node (ref "C4") (pin "2") (pinfunction "2_2") (pintype "input"))
      (node (ref "C5") (pin "1") (pinfunction "1_1") (pintype "unspecified"))
      (node (ref "C9") (pin "1") (pinfunction "1_1") (pintype "input"))
      (node (ref "L2") (pin "2") (pinfunction "2_2") (pintype "unspecified"))
      (node (ref "R3") (pin "2") (pinfunction "2_2") (pintype "input"))
      (node (ref "R6") (pin "2") (pinfunction "2_2") (pintype "input"))
      (node (ref "U1") (pin "2") (pinfunction "VCC_2") (pintype "input"))
      (node (ref "U1") (pin "4") (pinfunction "VCC_4") (pintype "input"))
      (node (ref "U2") (pin "1") (pinfunction "VIN_1") (pintype "unspecified"))
      (node (ref "U2") (pin "3") (pinfunction "EN_3") (pintype "unspecified"))
    )
    (net (code "2") (name "/02.6") (class "Default")
      (node (ref "R74") (pin "1") (pinfunction "1_1") (pintype "input"))
      (node (ref "U1") (pin "96") (pinfunction "02.6_96") (pintype "input"))
    )
    (net (code "3") (name "/02.7") (class "Default")
      (node (ref "R75") (pin "2") (pinfunction "2_2") (pintype "input"))
      (node (ref "U1") (pin "97") (pinfunction "02.7_97") (pintype "input"))
    )
    (net (code "4") (name "/10.1") (class "Default")
      (node (ref "CN4") (pin "3") (pinfunction "3_3") (pintype "unspecified"))
      (node (ref "U1") (pin "85") (pinfunction "10.1_85") (pintype "input"))
    )
    (net (code "5") (name "/10.3") (class "Default")
      (node (ref "CN4") (pin "4") (pinfunction "4_4") (pintype "unspecified"))
      (node (ref "U1") (pin "87") (pinfunction "10.3_87") (pintype "input"))
    )
    (net (code "6") (name "/10.5") (class "Default")
      (node (ref "U1") (pin "88") (pinfunction "10.5_88") (pintype "input"))
      (node (ref "U12") (pin "7") (pinfunction "RXD_7") (pintype "unspecified"))
    )
    (net (code "7") (name "/10.6") (class "Default")
      (node (ref "U1") (pin "89") (pinfunction "10.6_89") (pintype "input"))
      (node (ref "U12") (pin "6") (pinfunction "TXD_6") (pintype "unspecified"))
    )
    (net (code "8") (name "/11.2") (class "Default")
      (node (ref "R48") (pin "2") (pinfunction "2_2") (pintype "input"))
      (node (ref "U1") (pin "78") (pinfunction "11.2_78") (pintype "input"))
    )
    (net (code "9") (name "/11.3") (class "Default")
      (node (ref "R47") (pin "2") (pinfunction "2_2") (pintype "input"))
      (node (ref "U1") (pin "79") (pinfunction "11.3_79") (pintype "input"))
    )
    (net (code "10") (name "/15.0") (class "Default")
      (node (ref "H6") (pin "6") (pinfunction "6_6") (pintype "unspecified"))
      (node (ref "U1") (pin "58") (pinfunction "15.0_58") (pintype "input"))
    )
    (net (code "11") (name "/15.1") (class "Default")
      (node (ref "H6") (pin "5") (pinfunction "5_5") (pintype "unspecified"))
      (node (ref "U1") (pin "59") (pinfunction "15.1_59") (pintype "input"))
    )
    (net (code "12") (name "/15.2") (class "Default")
      (node (ref "H6") (pin "7") (pinfunction "7_7") (pintype "unspecified"))
      (node (ref "U1") (pin "60") (pinfunction "15.2_60") (pintype "input"))
    )
    (net (code "13") (name "/15.3") (class "Default")
      (node (ref "H6") (pin "3") (pinfunction "3_3") (pintype "unspecified"))
      (node (ref "U1") (pin "61") (pinfunction "15.3_61") (pintype "input"))
    )
    (net (code "14") (name "/15.4") (class "Default")
      (node (ref "H6") (pin "8") (pinfunction "8_8") (pintype "unspecified"))
      (node (ref "U1") (pin "62") (pinfunction "15.4_62") (pintype "input"))
    )
    (net (code "15") (name "/15.5") (class "Default")
      (node (ref "H6") (pin "4") (pinfunction "4_4") (pintype "unspecified"))
      (node (ref "U1") (pin "63") (pinfunction "15.5_63") (pintype "input"))
    )
    (net (code "16") (name "/20.6") (class "Default")
      (node (ref "R45") (pin "2") (pinfunction "2_2") (pintype "input"))
      (node (ref "U1") (pin "49") (pinfunction "20.6_49") (pintype "input"))
    )
    (net (code "17") (name "/20.7") (class "Default")
      (node (ref "R46") (pin "2") (pinfunction "2_2") (pintype "input"))
      (node (ref "U1") (pin "50") (pinfunction "20.7_50") (pintype "input"))
    )
    (net (code "18") (name "/20.11") (class "Default")
      (node (ref "H5") (pin "3") (pinfunction "3_3") (pintype "unspecified"))
      (node (ref "U1") (pin "54") (pinfunction "20.11_54") (pintype "input"))
    )
    (net (code "19") (name "/20.12") (class "Default")
      (node (ref "H5") (pin "5") (pinfunction "5_5") (pintype "unspecified"))
      (node (ref "U1") (pin "55") (pinfunction "20.12_55") (pintype "input"))
    )
    (net (code "20") (name "/20.13") (class "Default")
      (node (ref "H5") (pin "6") (pinfunction "6_6") (pintype "unspecified"))
      (node (ref "U1") (pin "56") (pinfunction "20.13_56") (pintype "input"))
    )
    (net (code "21") (name "/20.14") (class "Default")
      (node (ref "H5") (pin "4") (pinfunction "4_4") (pintype "unspecified"))
      (node (ref "U1") (pin "57") (pinfunction "20.14_57") (pintype "input"))
    )
    (net (code "22") (name "/33.9") (class "Default")
      (node (ref "R73") (pin "1") (pinfunction "1_1") (pintype "input"))
      (node (ref "U1") (pin "27") (pinfunction "33.9_27") (pintype "input"))
    )
    (net (code "23") (name "/33.10") (class "Default")
      (node (ref "R38") (pin "1") (pinfunction "1_1") (pintype "input"))
      (node (ref "R40") (pin "1") (pinfunction "1_1") (pintype "input"))
      (node (ref "U1") (pin "28") (pinfunction "33.10_28") (pintype "input"))
    )
    (net (code "24") (name "/D+") (class "Default")
      (node (ref "R69") (pin "1") (pinfunction "1_1") (pintype "input"))
      (node (ref "U15") (pin "A6") (pinfunction "D+_A6") (pintype "unspecified"))
      (node (ref "U15") (pin "B6") (pinfunction "D+_B6") (pintype "unspecified"))
    )
    (net (code "25") (name "/D-") (class "Default")
      (node (ref "R70") (pin "1") (pinfunction "1_1") (pintype "input"))
      (node (ref "U15") (pin "A7") (pinfunction "D-_A7") (pintype "unspecified"))
      (node (ref "U15") (pin "B7") (pinfunction "D-_B7") (pintype "unspecified"))
    )
    (net (code "26") (name "/FEEDBACK1") (class "Default")
      (node (ref "R5") (pin "2") (pinfunction "2_2") (pintype "unspecified"))
      (node (ref "R7") (pin "1") (pinfunction "1_1") (pintype "input"))
      (node (ref "U6") (pin "5") (pinfunction "FB_5") (pintype "input"))
    )
    (net (code "27") (name "/FEEDBACK2") (class "Default")
      (node (ref "R19") (pin "2") (pinfunction "2_2") (pintype "input"))
      (node (ref "R42") (pin "1") (pinfunction "1_1") (pintype "unspecified"))
      (node (ref "U4") (pin "5") (pinfunction "FB_5") (pintype "input"))
    )
    (net (code "28") (name "12V") (class "Default")
      (node (ref "C20") (pin "2") (pinfunction "2_2") (pintype "input"))
      (node (ref "C21") (pin "2") (pinfunction "2_2") (pintype "unspecified"))
      (node (ref "C26") (pin "1") (pinfunction "1_1") (pintype "input"))
      (node (ref "D1") (pin "1") (pinfunction "A_1") (pintype "input"))
      (node (ref "Q1") (pin "1") (pinfunction "D_1") (pintype "input"))
      (node (ref "U10") (pin "2") (pinfunction "+_2") (pintype "unspecified"))
      (node (ref "U4") (pin "2") (pinfunction "VIN_2") (pintype "input"))
      (node (ref "U4") (pin "3") (pinfunction "EN_3") (pintype "input"))
    )
    (net (code "29") (name "GND") (class "Default")
      (node (ref "C10") (pin "1") (pinfunction "1_1") (pintype "unspecified"))
      (node (ref "C11") (pin "2") (pinfunction "2_2") (pintype "unspecified"))
      (node (ref "C14") (pin "2") (pinfunction "2_2") (pintype "input"))
      (node (ref "C2") (pin "1") (pinfunction "1_1") (pintype "unspecified"))
      (node (ref "C20") (pin "1") (pinfunction "1_1") (pintype "input"))
      (node (ref "C21") (pin "1") (pinfunction "1_1") (pintype "unspecified"))
      (node (ref "C22") (pin "1") (pinfunction "1_1") (pintype "unspecified"))
      (node (ref "C23") (pin "1") (pinfunction "1_1") (pintype "input"))
      (node (ref "C25") (pin "2") (pinfunction "2_2") (pintype "input"))
      (node (ref "C26") (pin "2") (pinfunction "2_2") (pintype "input"))
      (node (ref "C28") (pin "1") (pinfunction "1_1") (pintype "unspecified"))
      (node (ref "C3") (pin "1") (pinfunction "1_1") (pintype "unspecified"))
      (node (ref "C30") (pin "1") (pinfunction "1_1") (pintype "input"))
      (node (ref "C39") (pin "2") (pinfunction "2_2") (pintype "unspecified"))
      (node (ref "C4") (pin "1") (pinfunction "1_1") (pintype "input"))
      (node (ref "C40") (pin "1") (pinfunction "1_1") (pintype "unspecified"))
      (node (ref "C5") (pin "2") (pinfunction "2_2") (pintype "unspecified"))
      (node (ref "C7") (pin "2") (pinfunction "2_2") (pintype "unspecified"))
      (node (ref "C9") (pin "2") (pinfunction "2_2") (pintype "input"))
      (node (ref "CN3") (pin "2") (pinfunction "2_2") (pintype "unspecified"))
      (node (ref "CN4") (pin "2") (pinfunction "2_2") (pintype "unspecified"))
      (node (ref "CN5") (pin "2") (pinfunction "2_2") (pintype "unspecified"))
      (node (ref "H2") (pin "1") (pinfunction "1_1") (pintype "input"))
      (node (ref "H5") (pin "2") (pinfunction "2_2") (pintype "unspecified"))
      (node (ref "H6") (pin "1") (pinfunction "1_1") (pintype "unspecified"))
      (node (ref "KEY1") (pin "0") (pinfunction "0_0") (pintype "input"))
      (node (ref "KEY1") (pin "2") (pinfunction "2_2") (pintype "input"))
      (node (ref "LED2") (pin "1") (pinfunction "-_1") (pintype "input"))
      (node (ref "LED3V3") (pin "2") (pinfunction "C_2") (pintype "input"))
      (node (ref "LED5V1") (pin "1") (pinfunction "C_1") (pintype "input"))
      (node (ref "LEDSTEER1") (pin "1") (pinfunction "C_1") (pintype "input"))
      (node (ref "Q2") (pin "2") (pinfunction "E_2") (pintype "unspecified"))
      (node (ref "R1") (pin "1") (pinfunction "1_1") (pintype "input"))
      (node (ref "R10") (pin "1") (pinfunction "1_1") (pintype "input"))
      (node (ref "R19") (pin "1") (pinfunction "1_1") (pintype "input"))
      (node (ref "R40") (pin "2") (pinfunction "2_2") (pintype "input"))
      (node (ref "R43") (pin "1") (pinfunction "1_1") (pintype "input"))
      (node (ref "R5") (pin "1") (pinfunction "1_1") (pintype "unspecified"))
      (node (ref "R71") (pin "2") (pinfunction "2_2") (pintype "unspecified"))
      (node (ref "R72") (pin "1") (pinfunction "1_1") (pintype "unspecified"))
      (node (ref "SW1") (pin "2") (pinfunction "2_2") (pintype "unspecified"))
      (node (ref "SW3") (pin "2") (pinfunction "2_2") (pintype "unspecified"))
      (node (ref "SW4") (pin "2") (pinfunction "2_2") (pintype "unspecified"))
      (node (ref "U1") (pin "1") (pinfunction "GND_1") (pintype "input"))
      (node (ref "U1") (pin "3") (pinfunction "GND_3") (pintype "input"))
      (node (ref "U10") (pin "1") (pinfunction "-_1") (pintype "unspecified"))
      (node (ref "U12") (pin "3") (pinfunction "GND_3") (pintype "unspecified"))
      (node (ref "U15") (pin "A1") (pinfunction "GND_A1") (pintype "unspecified"))
      (node (ref "U15") (pin "A12") (pinfunction "GND_A12") (pintype "unspecified"))
      (node (ref "U15") (pin "B1") (pinfunction "GND_B1") (pintype "unspecified"))
      (node (ref "U15") (pin "B12") (pinfunction "GND_B12") (pintype "unspecified"))
      (node (ref "U2") (pin "2") (pinfunction "GND_2") (pintype "unspecified"))
      (node (ref "U4") (pin "7") (pinfunction "GND_7") (pintype "input"))
      (node (ref "U4") (pin "9") (pinfunction "EP_9") (pintype "input"))
      (node (ref "U6") (pin "7") (pinfunction "GND_7") (pintype "input"))
      (node (ref "U6") (pin "9") (pinfunction "EP_9") (pintype "input"))
    )
    (net (code "30") (name "Net-(BUZZER2-+)") (class "Default")
      (node (ref "BUZZER2") (pin "1") (pinfunction "+_1") (pintype "unspecified"))
      (node (ref "R41") (pin "2") (pinfunction "2_2") (pintype "input"))
    )
    (net (code "31") (name "Net-(BUZZER2--)") (class "Default")
      (node (ref "BUZZER2") (pin "2") (pinfunction "-_2") (pintype "unspecified"))
      (node (ref "Q2") (pin "3") (pinfunction "C_3") (pintype "unspecified"))
    )
    (net (code "32") (name "Net-(C3-Pad2)") (class "Default")
      (node (ref "C3") (pin "2") (pinfunction "2_2") (pintype "unspecified"))
      (node (ref "R2") (pin "2") (pinfunction "2_2") (pintype "unspecified"))
    )
    (net (code "33") (name "Net-(C22-Pad2)") (class "Default")
      (node (ref "C22") (pin "2") (pinfunction "2_2") (pintype "unspecified"))
      (node (ref "R11") (pin "2") (pinfunction "2_2") (pintype "unspecified"))
    )
    (net (code "34") (name "Net-(CN5-Pad1)") (class "Default")
      (node (ref "CN5") (pin "1") (pinfunction "1_1") (pintype "unspecified"))
      (node (ref "R74") (pin "2") (pinfunction "2_2") (pintype "input"))
    )
    (net (code "35") (name "Net-(CN5-Pad3)") (class "Default")
      (node (ref "CN5") (pin "3") (pinfunction "3_3") (pintype "unspecified"))
      (node (ref "R75") (pin "1") (pinfunction "1_1") (pintype "input"))
    )
    (net (code "36") (name "Net-(D1-K)") (class "Default")
      (node (ref "C14") (pin "1") (pinfunction "1_1") (pintype "input"))
      (node (ref "C2") (pin "2") (pinfunction "2_2") (pintype "unspecified"))
      (node (ref "C30") (pin "2") (pinfunction "2_2") (pintype "input"))
      (node (ref "D1") (pin "2") (pinfunction "K_2") (pintype "input"))
      (node (ref "U6") (pin "2") (pinfunction "VIN_2") (pintype "input"))
      (node (ref "U6") (pin "3") (pinfunction "EN_3") (pintype "input"))
    )
    (net (code "37") (name "Net-(D2-Pad2)") (class "Default")
      (node (ref "D2") (pin "2") (pinfunction "2_2") (pintype "unspecified"))
      (node (ref "R43") (pin "2") (pinfunction "2_2") (pintype "input"))
      (node (ref "U16") (pin "1") (pinfunction "1_1") (pintype "unspecified"))
    )
    (net (code "38") (name "Net-(H2-Pad3)") (class "Default")
      (node (ref "H2") (pin "3") (pinfunction "3_3") (pintype "input"))
      (node (ref "R73") (pin "2") (pinfunction "2_2") (pintype "input"))
    )
    (net (code "39") (name "Net-(KEY1-Pad1)") (class "Default")
      (node (ref "KEY1") (pin "1") (pinfunction "1_1") (pintype "input"))
      (node (ref "R47") (pin "1") (pinfunction "1_1") (pintype "input"))
      (node (ref "R53") (pin "2") (pinfunction "2_2") (pintype "input"))
    )
    (net (code "40") (name "Net-(LED2-+)") (class "Default")
      (node (ref "LED2") (pin "2") (pinfunction "+_2") (pintype "input"))
      (node (ref "R68") (pin "2") (pinfunction "2_2") (pintype "input"))
    )
    (net (code "41") (name "Net-(LED3V3-A)") (class "Default")
      (node (ref "LED3V3") (pin "1") (pinfunction "A_1") (pintype "input"))
      (node (ref "R20") (pin "2") (pinfunction "2_2") (pintype "input"))
    )
    (net (code "42") (name "Net-(LED5V1-A)") (class "Default")
      (node (ref "LED5V1") (pin "2") (pinfunction "A_2") (pintype "input"))
      (node (ref "R6") (pin "1") (pinfunction "1_1") (pintype "input"))
    )
    (net (code "43") (name "Net-(LEDSTEER1-A)") (class "Default")
      (node (ref "LEDSTEER1") (pin "2") (pinfunction "A_2") (pintype "input"))
      (node (ref "R16") (pin "1") (pinfunction "1_1") (pintype "input"))
    )
    (net (code "44") (name "Net-(Q1-G)") (class "Default")
      (node (ref "Q1") (pin "2") (pinfunction "G_2") (pintype "input"))
      (node (ref "U16") (pin "2") (pinfunction "2_2") (pintype "unspecified"))
    )
    (net (code "45") (name "Net-(Q1-S)") (class "Default")
      (node (ref "CN3") (pin "1") (pinfunction "1_1") (pintype "unspecified"))
      (node (ref "D2") (pin "1") (pinfunction "1_1") (pintype "unspecified"))
      (node (ref "Q1") (pin "3") (pinfunction "S_3") (pintype "input"))
      (node (ref "U16") (pin "3") (pinfunction "3_3") (pintype "unspecified"))
    )
    (net (code "46") (name "Net-(Q2-B)") (class "Default")
      (node (ref "Q2") (pin "1") (pinfunction "B_1") (pintype "unspecified"))
      (node (ref "R38") (pin "2") (pinfunction "2_2") (pintype "input"))
    )
    (net (code "47") (name "Net-(R3-Pad1)") (class "Default")
      (node (ref "R3") (pin "1") (pinfunction "1_1") (pintype "input"))
      (node (ref "R7") (pin "2") (pinfunction "2_2") (pintype "input"))
    )
    (net (code "48") (name "Net-(R17-Pad1)") (class "Default")
      (node (ref "R17") (pin "1") (pinfunction "1_1") (pintype "input"))
      (node (ref "R42") (pin "2") (pinfunction "2_2") (pintype "unspecified"))
      (node (ref "R42") (pin "3") (pinfunction "3_3") (pintype "unspecified"))
    )
    (net (code "49") (name "Net-(R45-Pad1)") (class "Default")
      (node (ref "R45") (pin "1") (pinfunction "1_1") (pintype "input"))
      (node (ref "R51") (pin "2") (pinfunction "2_2") (pintype "input"))
      (node (ref "SW1") (pin "1") (pinfunction "1_1") (pintype "unspecified"))
    )
    (net (code "50") (name "Net-(R46-Pad1)") (class "Default")
      (node (ref "R46") (pin "1") (pinfunction "1_1") (pintype "input"))
      (node (ref "R52") (pin "2") (pinfunction "2_2") (pintype "input"))
      (node (ref "SW3") (pin "1") (pinfunction "1_1") (pintype "unspecified"))
    )
    (net (code "51") (name "Net-(R48-Pad1)") (class "Default")
      (node (ref "R48") (pin "1") (pinfunction "1_1") (pintype "input"))
      (node (ref "R60") (pin "2") (pinfunction "2_2") (pintype "input"))
      (node (ref "SW4") (pin "1") (pinfunction "1_1") (pintype "unspecified"))
    )
    (net (code "52") (name "Net-(U4-BOOT)") (class "Default")
      (node (ref "C24") (pin "1") (pinfunction "1_1") (pintype "unspecified"))
      (node (ref "U4") (pin "1") (pinfunction "BOOT_1") (pintype "input"))
    )
    (net (code "53") (name "Net-(U4-COMP)") (class "Default")
      (node (ref "R11") (pin "1") (pinfunction "1_1") (pintype "unspecified"))
      (node (ref "U4") (pin "6") (pinfunction "COMP_6") (pintype "input"))
    )
    (net (code "54") (name "Net-(U4-RT{slash}CLK)") (class "Default")
      (node (ref "R10") (pin "2") (pinfunction "2_2") (pintype "input"))
      (node (ref "U4") (pin "4") (pinfunction "RT/CLK_4") (pintype "input"))
    )
    (net (code "55") (name "Net-(U4-SW)") (class "Default")
      (node (ref "C24") (pin "2") (pinfunction "2_2") (pintype "unspecified"))
      (node (ref "L3") (pin "1") (pinfunction "1_1") (pintype "unspecified"))
      (node (ref "U4") (pin "8") (pinfunction "SW_8") (pintype "input"))
    )
    (net (code "56") (name "Net-(U6-BOOT)") (class "Default")
      (node (ref "C6") (pin "1") (pinfunction "1_1") (pintype "unspecified"))
      (node (ref "U6") (pin "1") (pinfunction "BOOT_1") (pintype "input"))
    )
    (net (code "57") (name "Net-(U6-COMP)") (class "Default")
      (node (ref "R2") (pin "1") (pinfunction "1_1") (pintype "unspecified"))
      (node (ref "U6") (pin "6") (pinfunction "COMP_6") (pintype "input"))
    )
    (net (code "58") (name "Net-(U6-RT{slash}CLK)") (class "Default")
      (node (ref "R1") (pin "2") (pinfunction "2_2") (pintype "input"))
      (node (ref "U6") (pin "4") (pinfunction "RT/CLK_4") (pintype "input"))
    )
    (net (code "59") (name "Net-(U6-SW)") (class "Default")
      (node (ref "C6") (pin "2") (pinfunction "2_2") (pintype "unspecified"))
      (node (ref "L2") (pin "1") (pinfunction "1_1") (pintype "unspecified"))
      (node (ref "U6") (pin "8") (pinfunction "SW_8") (pintype "input"))
    )
    (net (code "60") (name "Net-(U12-UD+)") (class "Default")
      (node (ref "R69") (pin "2") (pinfunction "2_2") (pintype "input"))
      (node (ref "U12") (pin "1") (pinfunction "UD+_1") (pintype "unspecified"))
    )
    (net (code "61") (name "Net-(U12-UD-)") (class "Default")
      (node (ref "R70") (pin "2") (pinfunction "2_2") (pintype "input"))
      (node (ref "U12") (pin "2") (pinfunction "UD-_2") (pintype "unspecified"))
    )
    (net (code "62") (name "Net-(U12-V3)") (class "Default")
      (node (ref "C40") (pin "2") (pinfunction "2_2") (pintype "unspecified"))
      (node (ref "U12") (pin "8") (pinfunction "V3_8") (pintype "unspecified"))
    )
    (net (code "63") (name "Net-(U15-CC1)") (class "Default")
      (node (ref "R72") (pin "2") (pinfunction "2_2") (pintype "unspecified"))
      (node (ref "U15") (pin "A5") (pinfunction "CC1_A5") (pintype "unspecified"))
    )
    (net (code "64") (name "Net-(U15-CC2)") (class "Default")
      (node (ref "R71") (pin "1") (pinfunction "1_1") (pintype "unspecified"))
      (node (ref "U15") (pin "B5") (pinfunction "CC2_B5") (pintype "unspecified"))
    )
    (net (code "65") (name "VBUS") (class "Default")
      (node (ref "C11") (pin "1") (pinfunction "1_1") (pintype "unspecified"))
      (node (ref "C39") (pin "1") (pinfunction "1_1") (pintype "unspecified"))
      (node (ref "R68") (pin "1") (pinfunction "1_1") (pintype "input"))
      (node (ref "U12") (pin "5") (pinfunction "VCC_5") (pintype "unspecified"))
      (node (ref "U15") (pin "A4") (pinfunction "VBUS_A4") (pintype "unspecified"))
      (node (ref "U15") (pin "A9") (pinfunction "VBUS_A9") (pintype "unspecified"))
      (node (ref "U15") (pin "B4") (pinfunction "VBUS_B4") (pintype "unspecified"))
      (node (ref "U15") (pin "B9") (pinfunction "VBUS_B9") (pintype "unspecified"))
    )
    (net (code "66") (name "VCC3V3") (class "Default")
      (node (ref "C28") (pin "2") (pinfunction "2_2") (pintype "unspecified"))
      (node (ref "C7") (pin "1") (pinfunction "1_1") (pintype "unspecified"))
      (node (ref "CN4") (pin "1") (pinfunction "1_1") (pintype "unspecified"))
      (node (ref "H5") (pin "1") (pinfunction "1_1") (pintype "unspecified"))
      (node (ref "H6") (pin "2") (pinfunction "2_2") (pintype "unspecified"))
      (node (ref "R20") (pin "1") (pinfunction "1_1") (pintype "input"))
      (node (ref "R41") (pin "1") (pinfunction "1_1") (pintype "input"))
      (node (ref "R51") (pin "1") (pinfunction "1_1") (pintype "input"))
      (node (ref "R52") (pin "1") (pinfunction "1_1") (pintype "input"))
      (node (ref "R53") (pin "1") (pinfunction "1_1") (pintype "input"))
      (node (ref "R60") (pin "1") (pinfunction "1_1") (pintype "input"))
      (node (ref "U2") (pin "5") (pinfunction "VOUT_5") (pintype "unspecified"))
    )
    (net (code "67") (name "VCCSTEER") (class "Default")
      (node (ref "C23") (pin "2") (pinfunction "2_2") (pintype "input"))
      (node (ref "C25") (pin "1") (pinfunction "1_1") (pintype "input"))
      (node (ref "H2") (pin "2") (pinfunction "2_2") (pintype "input"))
      (node (ref "L3") (pin "2") (pinfunction "2_2") (pintype "unspecified"))
      (node (ref "R16") (pin "2") (pinfunction "2_2") (pintype "input"))
      (node (ref "R17") (pin "2") (pinfunction "2_2") (pintype "input"))
    )
    (net (code "68") (name "unconnected-(SCREW1-Pad1)") (class "Default")
      (node (ref "SCREW1") (pin "1") (pinfunction "1_1") (pintype "input+no_connect"))
    )
    (net (code "69") (name "unconnected-(SCREW2-Pad1)") (class "Default")
      (node (ref "SCREW2") (pin "1") (pinfunction "1_1") (pintype "input+no_connect"))
    )
    (net (code "70") (name "unconnected-(SCREW3-Pad1)") (class "Default")
      (node (ref "SCREW3") (pin "1") (pinfunction "1_1") (pintype "input+no_connect"))
    )
    (net (code "71") (name "unconnected-(SCREW4-Pad1)") (class "Default")
      (node (ref "SCREW4") (pin "1") (pinfunction "1_1") (pintype "input+no_connect"))
    )
    (net (code "72") (name "unconnected-(U1-00.0-Pad99)") (class "Default")
      (node (ref "U1") (pin "99") (pinfunction "00.0_99") (pintype "input+no_connect"))
    )
    (net (code "73") (name "unconnected-(U1-00.1-Pad100)") (class "Default")
      (node (ref "U1") (pin "100") (pinfunction "00.1_100") (pintype "input+no_connect"))
    )
    (net (code "74") (name "unconnected-(U1-00.2-Pad101)") (class "Default")
      (node (ref "U1") (pin "101") (pinfunction "00.2_101") (pintype "input+no_connect"))
    )
    (net (code "75") (name "unconnected-(U1-00.3-Pad102)") (class "Default")
      (node (ref "U1") (pin "102") (pinfunction "00.3_102") (pintype "input+no_connect"))
    )
    (net (code "76") (name "unconnected-(U1-00.4-Pad103)") (class "Default")
      (node (ref "U1") (pin "103") (pinfunction "00.4_103") (pintype "input+no_connect"))
    )
    (net (code "77") (name "unconnected-(U1-00.5-Pad104)") (class "Default")
      (node (ref "U1") (pin "104") (pinfunction "00.5_104") (pintype "input+no_connect"))
    )
    (net (code "78") (name "unconnected-(U1-00.6-Pad105)") (class "Default")
      (node (ref "U1") (pin "105") (pinfunction "00.6_105") (pintype "input+no_connect"))
    )
    (net (code "79") (name "unconnected-(U1-00.7-Pad106)") (class "Default")
      (node (ref "U1") (pin "106") (pinfunction "00.7_106") (pintype "input+no_connect"))
    )
    (net (code "80") (name "unconnected-(U1-00.8-Pad107)") (class "Default")
      (node (ref "U1") (pin "107") (pinfunction "00.8_107") (pintype "input+no_connect"))
    )
    (net (code "81") (name "unconnected-(U1-00.9-Pad108)") (class "Default")
      (node (ref "U1") (pin "108") (pinfunction "00.9_108") (pintype "input+no_connect"))
    )
    (net (code "82") (name "unconnected-(U1-02.0-Pad90)") (class "Default")
      (node (ref "U1") (pin "90") (pinfunction "02.0_90") (pintype "input+no_connect"))
    )
    (net (code "83") (name "unconnected-(U1-02.1-Pad91)") (class "Default")
      (node (ref "U1") (pin "91") (pinfunction "02.1_91") (pintype "input+no_connect"))
    )
    (net (code "84") (name "unconnected-(U1-02.2-Pad92)") (class "Default")
      (node (ref "U1") (pin "92") (pinfunction "02.2_92") (pintype "input+no_connect"))
    )
    (net (code "85") (name "unconnected-(U1-02.3-Pad93)") (class "Default")
      (node (ref "U1") (pin "93") (pinfunction "02.3_93") (pintype "input+no_connect"))
    )
    (net (code "86") (name "unconnected-(U1-02.4-Pad94)") (class "Default")
      (node (ref "U1") (pin "94") (pinfunction "02.4_94") (pintype "input+no_connect"))
    )
    (net (code "87") (name "unconnected-(U1-02.5-Pad95)") (class "Default")
      (node (ref "U1") (pin "95") (pinfunction "02.5_95") (pintype "input+no_connect"))
    )
    (net (code "88") (name "unconnected-(U1-02.8-Pad98)") (class "Default")
      (node (ref "U1") (pin "98") (pinfunction "02.8_98") (pintype "input+no_connect"))
    )
    (net (code "89") (name "unconnected-(U1-10.2-Pad86)") (class "Default")
      (node (ref "U1") (pin "86") (pinfunction "10.2_86") (pintype "input+no_connect"))
    )
    (net (code "90") (name "unconnected-(U1-11.6-Pad80)") (class "Default")
      (node (ref "U1") (pin "80") (pinfunction "11.6_80") (pintype "input+no_connect"))
    )
    (net (code "91") (name "unconnected-(U1-11.9-Pad81)") (class "Default")
      (node (ref "U1") (pin "81") (pinfunction "11.9_81") (pintype "input+no_connect"))
    )
    (net (code "92") (name "unconnected-(U1-11.10-Pad82)") (class "Default")
      (node (ref "U1") (pin "82") (pinfunction "11.10_82") (pintype "input+no_connect"))
    )
    (net (code "93") (name "unconnected-(U1-11.11-Pad83)") (class "Default")
      (node (ref "U1") (pin "83") (pinfunction "11.11_83") (pintype "input+no_connect"))
    )
    (net (code "94") (name "unconnected-(U1-11.12-Pad84)") (class "Default")
      (node (ref "U1") (pin "84") (pinfunction "11.12_84") (pintype "input+no_connect"))
    )
    (net (code "95") (name "unconnected-(U1-13.0-Pad74)") (class "Default")
      (node (ref "U1") (pin "74") (pinfunction "13.0_74") (pintype "input+no_connect"))
    )
    (net (code "96") (name "unconnected-(U1-13.1-Pad75)") (class "Default")
      (node (ref "U1") (pin "75") (pinfunction "13.1_75") (pintype "input+no_connect"))
    )
    (net (code "97") (name "unconnected-(U1-13.2-Pad76)") (class "Default")
      (node (ref "U1") (pin "76") (pinfunction "13.2_76") (pintype "input+no_connect"))
    )
    (net (code "98") (name "unconnected-(U1-13.3-Pad77)") (class "Default")
      (node (ref "U1") (pin "77") (pinfunction "13.3_77") (pintype "input+no_connect"))
    )
    (net (code "99") (name "unconnected-(U1-15.6-Pad64)") (class "Default")
      (node (ref "U1") (pin "64") (pinfunction "15.6_64") (pintype "input+no_connect"))
    )
    (net (code "100") (name "unconnected-(U1-15.7-Pad65)") (class "Default")
      (node (ref "U1") (pin "65") (pinfunction "15.7_65") (pintype "input+no_connect"))
    )
    (net (code "101") (name "unconnected-(U1-15.8-Pad66)") (class "Default")
      (node (ref "U1") (pin "66") (pinfunction "15.8_66") (pintype "input+no_connect"))
    )
    (net (code "102") (name "unconnected-(U1-20.0-Pad44)") (class "Default")
      (node (ref "U1") (pin "44") (pinfunction "20.0_44") (pintype "input+no_connect"))
    )
    (net (code "103") (name "unconnected-(U1-20.3-Pad46)") (class "Default")
      (node (ref "U1") (pin "46") (pinfunction "20.3_46") (pintype "input+no_connect"))
    )
    (net (code "104") (name "unconnected-(U1-20.10-Pad53)") (class "Default")
      (node (ref "U1") (pin "53") (pinfunction "20.10_53") (pintype "input+no_connect"))
    )
    (net (code "105") (name "unconnected-(U1-21.2-Pad38)") (class "Default")
      (node (ref "U1") (pin "38") (pinfunction "21.2_38") (pintype "input+no_connect"))
    )
    (net (code "106") (name "unconnected-(U1-21.3-Pad39)") (class "Default")
      (node (ref "U1") (pin "39") (pinfunction "21.3_39") (pintype "input+no_connect"))
    )
    (net (code "107") (name "unconnected-(U1-21.4-Pad40)") (class "Default")
      (node (ref "U1") (pin "40") (pinfunction "21.4_40") (pintype "input+no_connect"))
    )
    (net (code "108") (name "unconnected-(U1-21.5-Pad41)") (class "Default")
      (node (ref "U1") (pin "41") (pinfunction "21.5_41") (pintype "input+no_connect"))
    )
    (net (code "109") (name "unconnected-(U1-22.0-Pad34)") (class "Default")
      (node (ref "U1") (pin "34") (pinfunction "22.0_34") (pintype "input+no_connect"))
    )
    (net (code "110") (name "unconnected-(U1-22.1-Pad35)") (class "Default")
      (node (ref "U1") (pin "35") (pinfunction "22.1_35") (pintype "input+no_connect"))
    )
    (net (code "111") (name "unconnected-(U1-22.2-Pad36)") (class "Default")
      (node (ref "U1") (pin "36") (pinfunction "22.2_36") (pintype "input+no_connect"))
    )
    (net (code "112") (name "unconnected-(U1-22.3-Pad37)") (class "Default")
      (node (ref "U1") (pin "37") (pinfunction "22.3_37") (pintype "input+no_connect"))
    )
    (net (code "113") (name "unconnected-(U1-23.1-Pad33)") (class "Default")
      (node (ref "U1") (pin "33") (pinfunction "23.1_33") (pintype "input+no_connect"))
    )
    (net (code "114") (name "unconnected-(U1-33.4-Pad22)") (class "Default")
      (node (ref "U1") (pin "22") (pinfunction "33.4_22") (pintype "input+no_connect"))
    )
    (net (code "115") (name "unconnected-(U1-33.5-Pad23)") (class "Default")
      (node (ref "U1") (pin "23") (pinfunction "33.5_23") (pintype "input+no_connect"))
    )
    (net (code "116") (name "unconnected-(U1-33.6-Pad24)") (class "Default")
      (node (ref "U1") (pin "24") (pinfunction "33.6_24") (pintype "input+no_connect"))
    )
    (net (code "117") (name "unconnected-(U1-33.7-Pad25)") (class "Default")
      (node (ref "U1") (pin "25") (pinfunction "33.7_25") (pintype "input+no_connect"))
    )
    (net (code "118") (name "unconnected-(U1-33.11-Pad29)") (class "Default")
      (node (ref "U1") (pin "29") (pinfunction "33.11_29") (pintype "input+no_connect"))
    )
    (net (code "119") (name "unconnected-(U1-33.12-Pad30)") (class "Default")
      (node (ref "U1") (pin "30") (pinfunction "33.12_30") (pintype "input+no_connect"))
    )
    (net (code "120") (name "unconnected-(U1-A11-Pad11)") (class "Default")
      (node (ref "U1") (pin "11") (pinfunction "A11_11") (pintype "input+no_connect"))
    )
    (net (code "121") (name "unconnected-(U2-NC-Pad4)") (class "Default")
      (node (ref "U2") (pin "4") (pinfunction "NC_4") (pintype "unspecified+no_connect"))
    )
    (net (code "122") (name "unconnected-(U12-RTS#-Pad4)") (class "Default")
      (node (ref "U12") (pin "4") (pinfunction "RTS#_4") (pintype "unspecified+no_connect"))
    )
    (net (code "123") (name "unconnected-(U15-Pad0)") (class "Default")
      (node (ref "U15") (pin "0") (pinfunction "0_0") (pintype "unspecified+no_connect"))
    )
  )
)
